# MCP3421.net
KiCad netlist of a schematic drawn in EAGLE
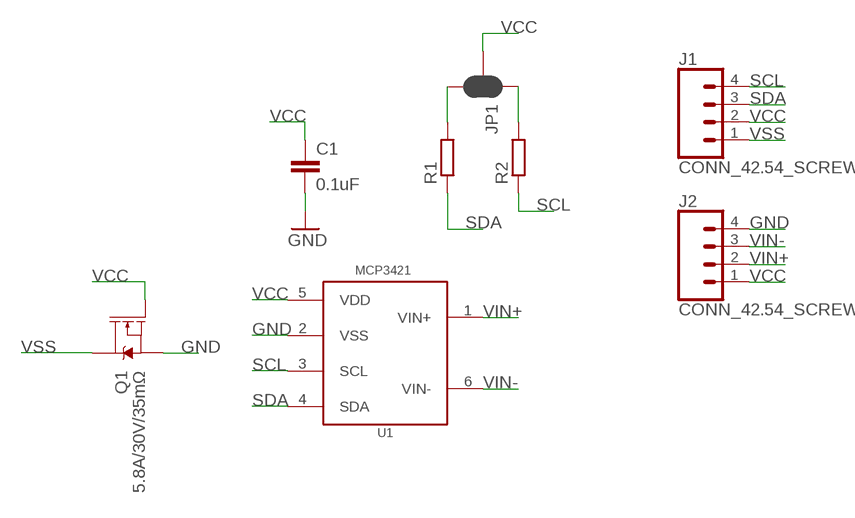
[diagram p0: schematic, sheet 1]

(export (version "E")
  (design (tool "Eeschema 10.0.6"))
  (components
    (comp (ref "C1")
      (value "0.1uF")
      (footprint "eagle-import:C0603")
      (fields (field (name "MF") "Murata") (field (name "MPN") "GCM188R71E104KA57D"))
      (libsource (lib "eagle-import") (part "C-EUC06030.1UF"))
    )
    (comp (ref "J1")
      (value "CONN_42.54_SCREW")
      (footprint "eagle-import:1X04_SCREW")
      (fields (field (name "MF") "On Shore") (field (name "MPN") "OSTVN04A150"))
      (libsource (lib "eagle-import") (part "CONN_42.54_SCREW"))
    )
    (comp (ref "J2")
      (value "CONN_42.54_SCREW")
      (footprint "eagle-import:1X04_SCREW")
      (fields (field (name "MF") "On Shore") (field (name "MPN") "OSTVN04A150"))
      (libsource (lib "eagle-import") (part "CONN_42.54_SCREW"))
    )
    (comp (ref "JP1")
      (value "JUMPER-SMT_3_2-NC_PASTE_SILK")
      (footprint "eagle-import:SMT-JUMPER_3_2-NC_PASTE_SILK")
      (libsource (lib "eagle-import") (part "JUMPER-SMT_3_2-NC_PASTE_SILK"))
    )
    (comp (ref "Q1")
      (value "5.8A/30V/35mΩ")
      (footprint "eagle-import:SOT23-3")
      (libsource (lib "eagle-import") (part "MOSFET-NCH-AO3404A"))
    )
    (comp (ref "R1")
      (value "R-EU_10KR0603")
      (footprint "eagle-import:R0603")
      (fields
        (field (name "MF") "Yageo")
        (field (name "MPN") "RC0603FR-0710KL")
        (field (name "VALUE_PART") "10k")
      )
      (libsource (lib "eagle-import") (part "R-EU_R060310K"))
    )
    (comp (ref "R2")
      (value "R-EU_10KR0603")
      (footprint "eagle-import:R0603")
      (fields
        (field (name "MF") "Yageo")
        (field (name "MPN") "RC0603FR-0710KL")
        (field (name "VALUE_PART") "10k")
      )
      (libsource (lib "eagle-import") (part "R-EU_R060310K"))
    )
    (comp (ref "U1")
      (value "MCP3421A3")
      (footprint "eagle-import:SOT23-6L")
      (fields
        (field (name "DISP") "MCP3421")
        (field (name "MF") "Microchip")
        (field (name "MPN") "MCP3421A3T-E/CH")
      )
      (libsource (lib "eagle-import") (part "MCP3421A3"))
    )
  )
  (nets
    (net (code "1") (name "/SCL") (class "Default")
      (node (ref "J1") (pin "4") (pinfunction "4_4") (pintype "passive"))
      (node (ref "R2") (pin "1") (pinfunction "1_1") (pintype "passive"))
      (node (ref "U1") (pin "3") (pinfunction "SCL_3") (pintype "bidirectional"))
    )
    (net (code "2") (name "/SDA") (class "Default")
      (node (ref "J1") (pin "3") (pinfunction "3_3") (pintype "passive"))
      (node (ref "R1") (pin "1") (pinfunction "1_1") (pintype "passive"))
      (node (ref "U1") (pin "4") (pinfunction "SDA_4") (pintype "bidirectional"))
    )
    (net (code "3") (name "/VCC") (class "Default")
      (node (ref "C1") (pin "1") (pinfunction "1_1") (pintype "passive"))
      (node (ref "J1") (pin "2") (pinfunction "2_2") (pintype "passive"))
      (node (ref "J2") (pin "1") (pinfunction "1_1") (pintype "passive"))
      (node (ref "JP1") (pin "2") (pinfunction "2_2") (pintype "passive"))
      (node (ref "Q1") (pin "1") (pinfunction "G_1") (pintype "bidirectional"))
      (node (ref "U1") (pin "5") (pinfunction "VDD_5") (pintype "passive"))
    )
    (net (code "4") (name "/VIN+") (class "Default")
      (node (ref "J2") (pin "2") (pinfunction "2_2") (pintype "passive"))
      (node (ref "U1") (pin "1") (pinfunction "VIN+_1") (pintype "input"))
    )
    (net (code "5") (name "/VIN-") (class "Default")
      (node (ref "J2") (pin "3") (pinfunction "3_3") (pintype "passive"))
      (node (ref "U1") (pin "6") (pinfunction "VIN-_6") (pintype "input"))
    )
    (net (code "6") (name "/VSS") (class "Default")
      (node (ref "J1") (pin "1") (pinfunction "1_1") (pintype "passive"))
      (node (ref "Q1") (pin "3") (pinfunction "D_3") (pintype "bidirectional"))
    )
    (net (code "7") (name "GND") (class "Default")
      (node (ref "C1") (pin "2") (pinfunction "2_2") (pintype "passive"))
      (node (ref "J2") (pin "4") (pinfunction "4_4") (pintype "passive"))
      (node (ref "Q1") (pin "2") (pinfunction "S_2") (pintype "bidirectional"))
      (node (ref "U1") (pin "2") (pinfunction "VSS_2") (pintype "passive"))
    )
    (net (code "8") (name "Net-(JP1-Pad1)") (class "Default")
      (node (ref "JP1") (pin "1") (pinfunction "1_1") (pintype "passive"))
      (node (ref "R2") (pin "2") (pinfunction "2_2") (pintype "passive"))
    )
    (net (code "9") (name "Net-(JP1-Pad3)") (class "Default")
      (node (ref "JP1") (pin "3") (pinfunction "3_3") (pintype "passive"))
      (node (ref "R1") (pin "2") (pinfunction "2_2") (pintype "passive"))
    )
  )
)
